# Siwa_PCB.net
KiCad netlist of a schematic drawn in Altium Designer
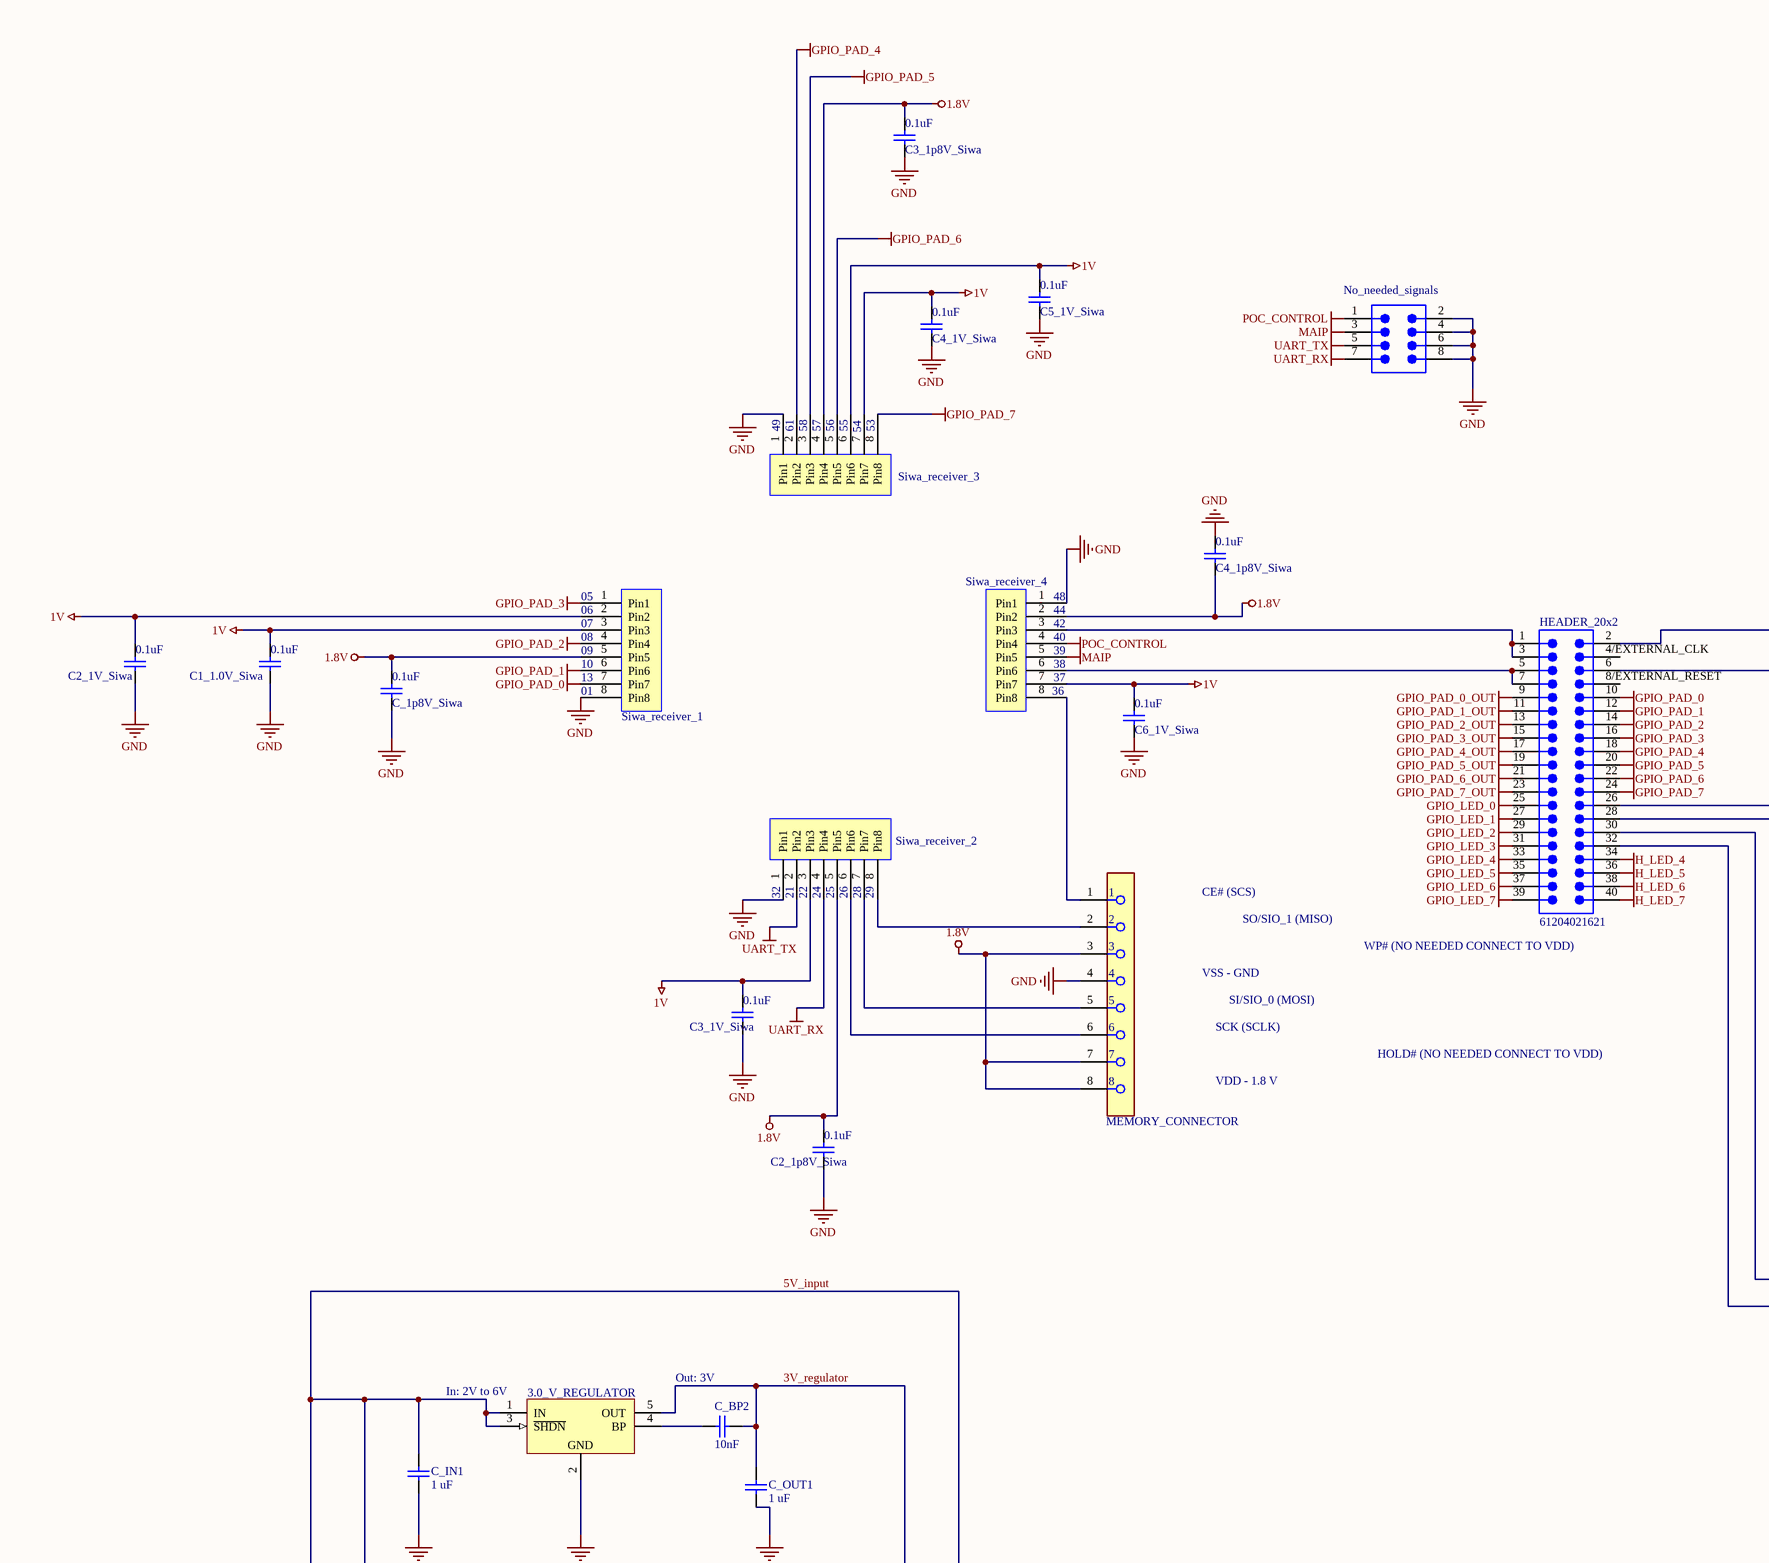
[diagram p0: Siwa_PCB.SchDoc, top left]
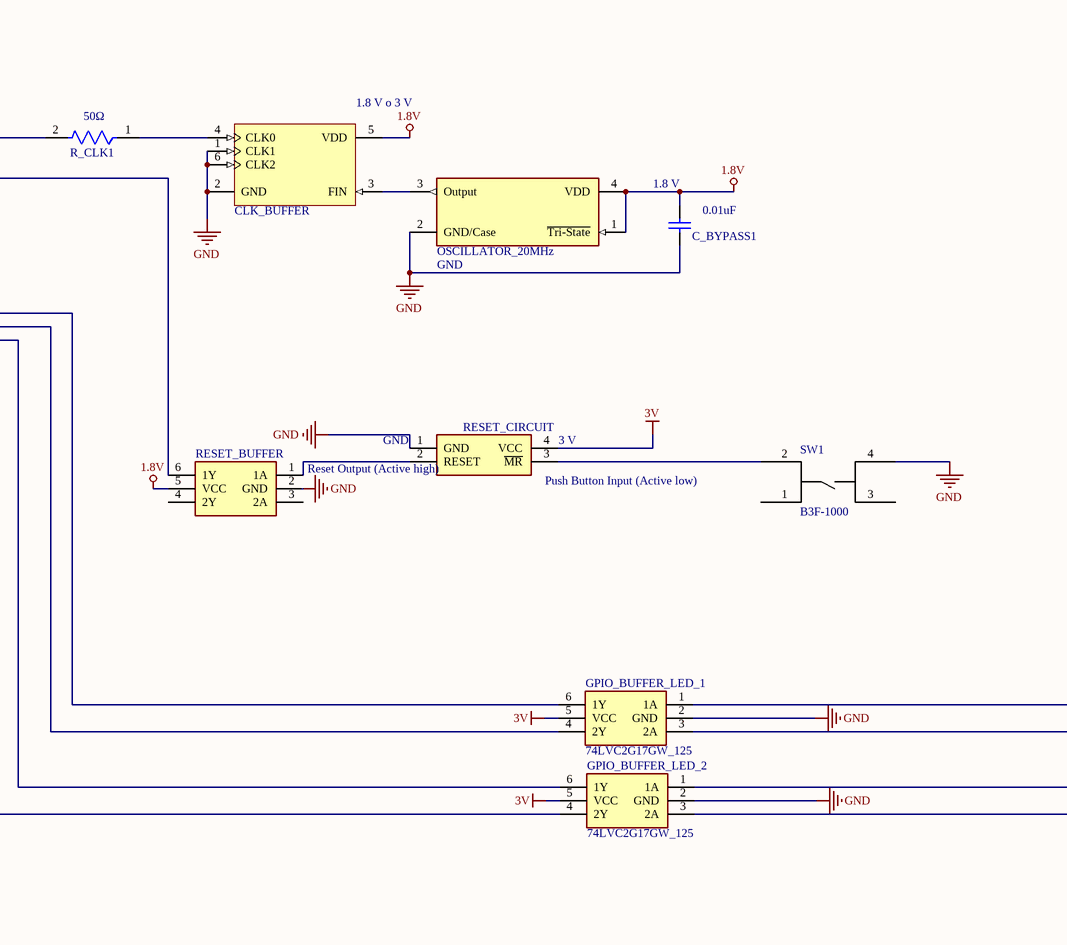
[diagram p1: Siwa_PCB.SchDoc, top right]
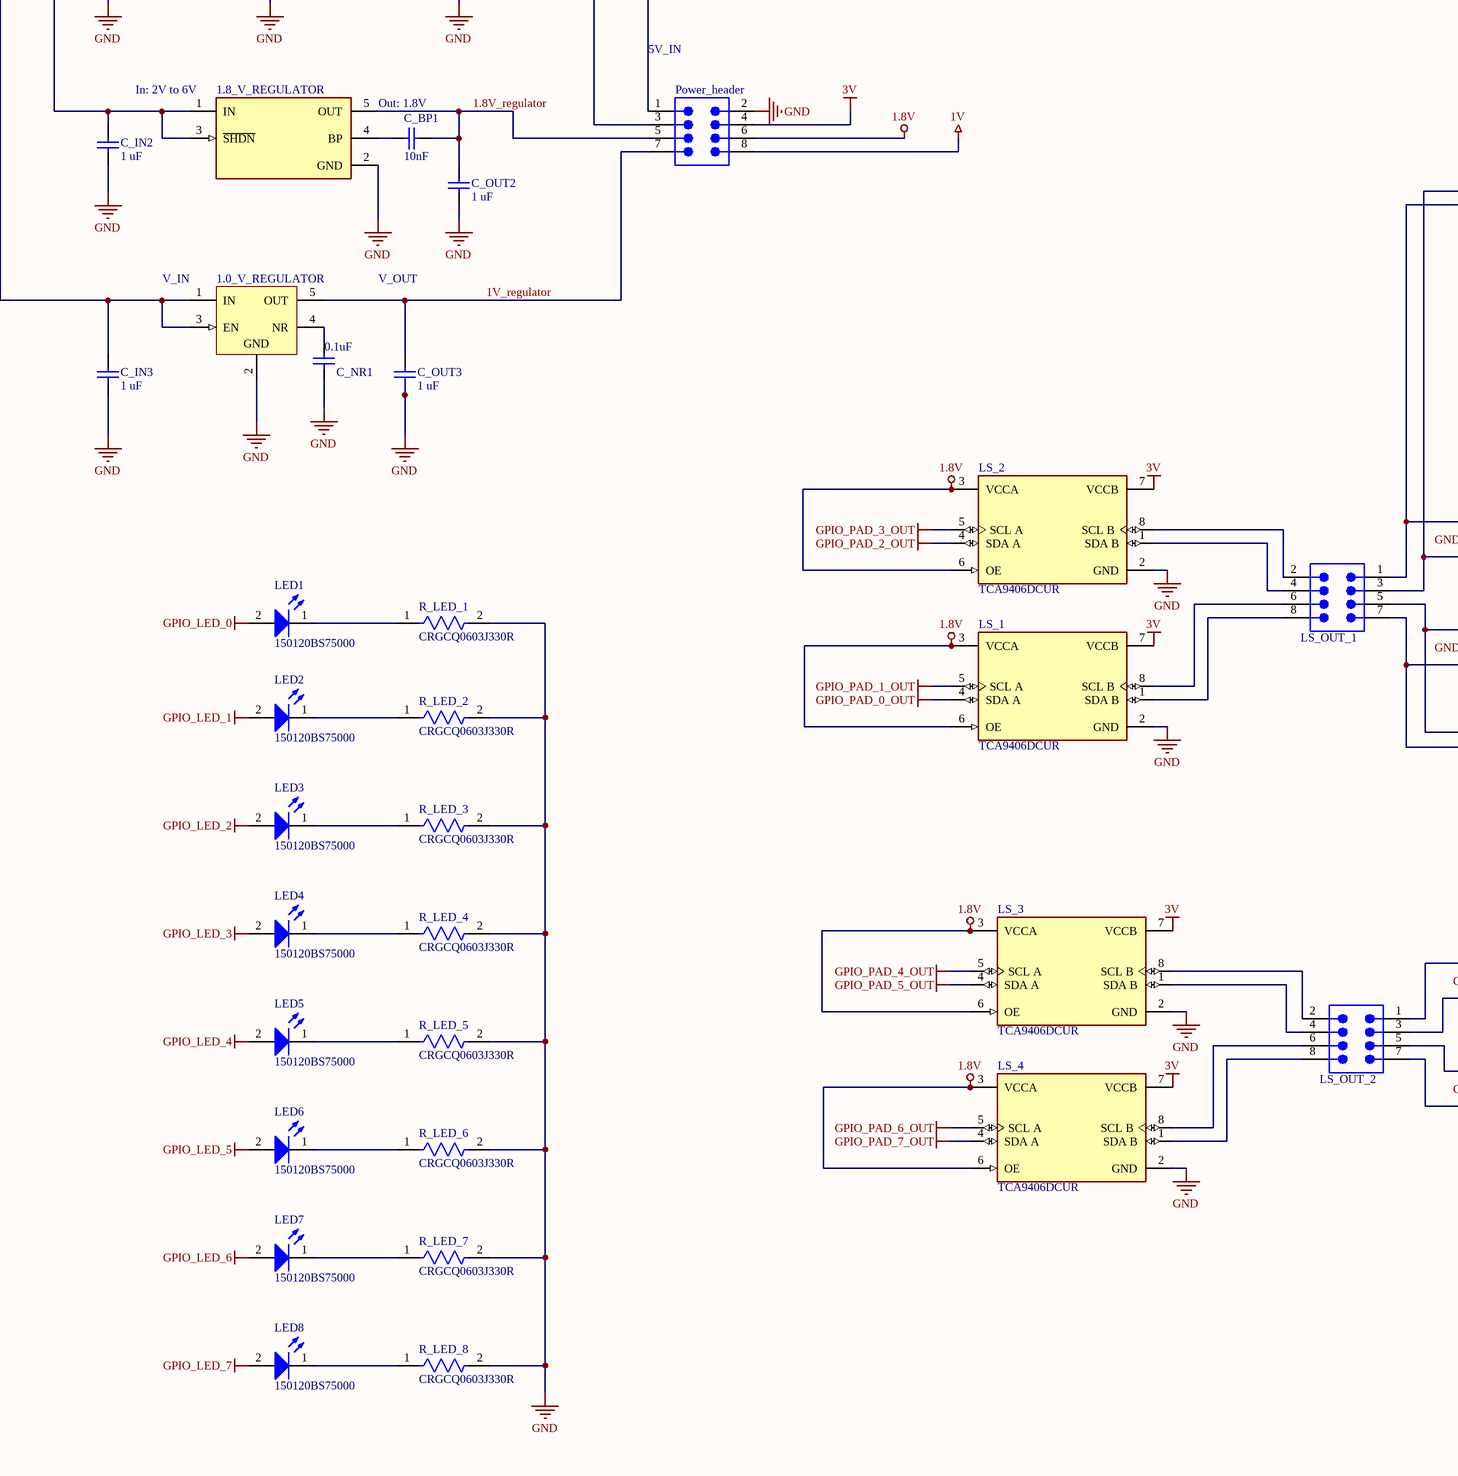
[diagram p2: Siwa_PCB.SchDoc, bottom left]
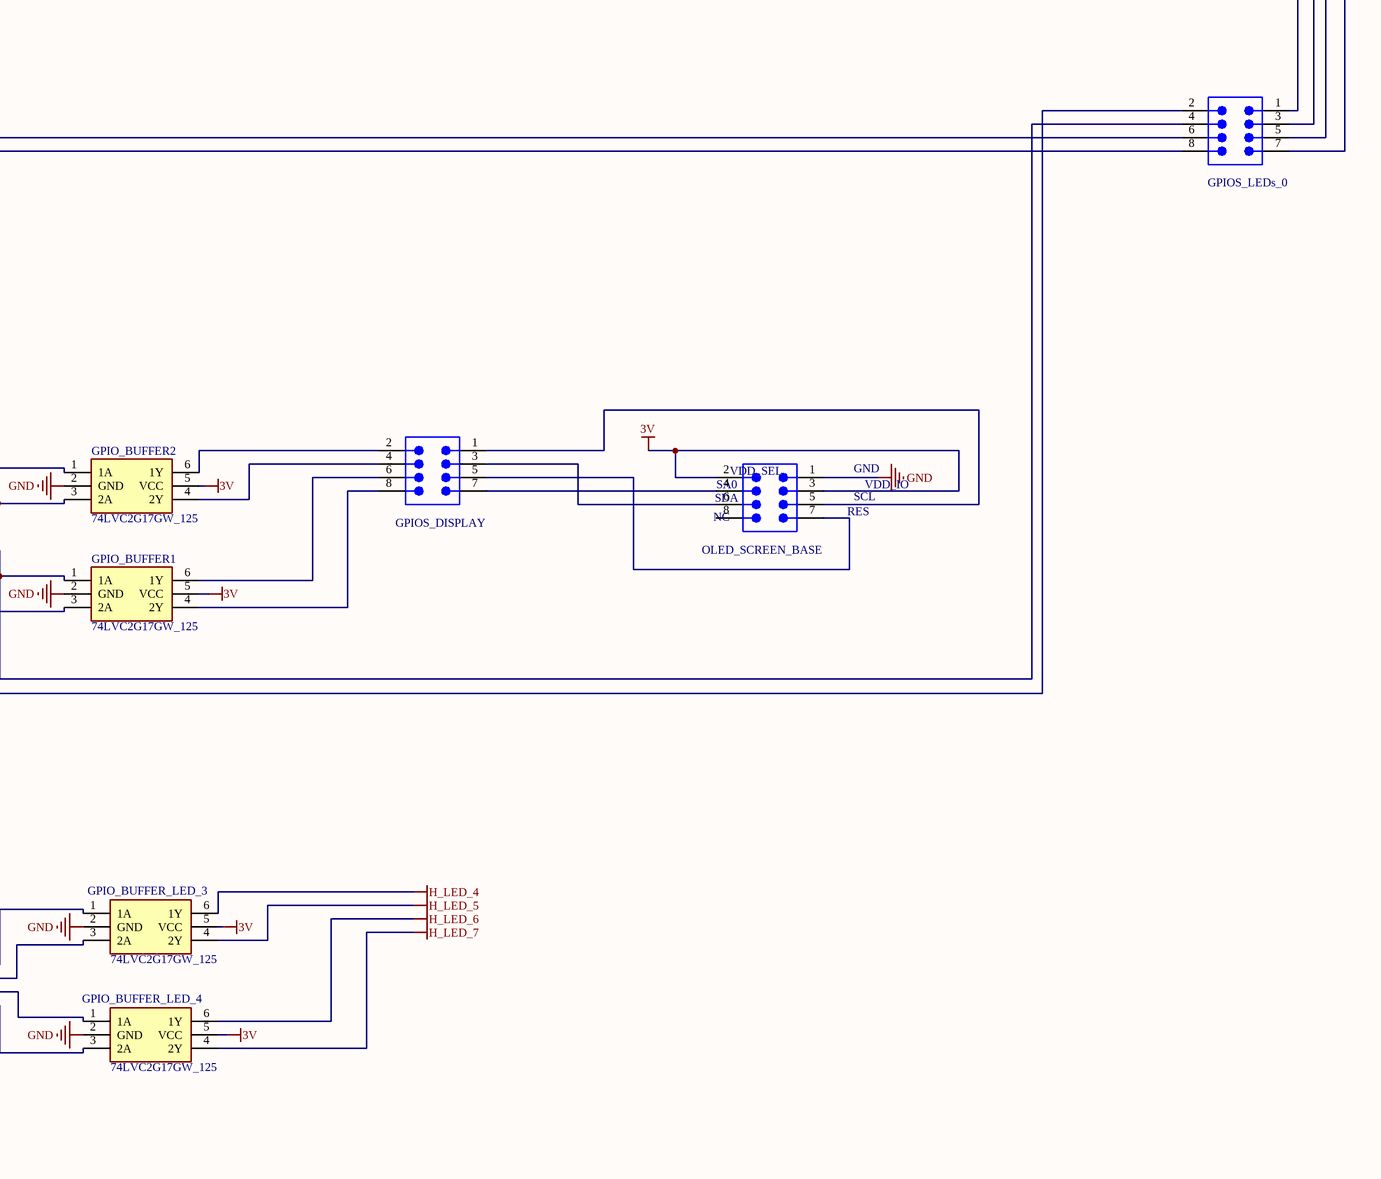
[diagram p3: Siwa_PCB.SchDoc, bottom right]

(export (version "E")
  (design (tool "Eeschema 10.0.6"))
  (components
    (comp (ref "1.0_V_REGULATOR")
      (value "TPS71710DCKT")
      (footprint "DCK0005A_M")
      (fields (field (name "MANUFACTURER") "Texas Instruments"))
      (libsource (lib "Altium Content Vault") (part "TI-TPS79NXX-YYSOT5"))
    )
    (comp (ref "1.8_V_REGULATOR")
      (value "MAX8510EXK18+T")
      (footprint "FP-X5-1-MFG")
      (description "IC REG LINEAR 1.8V 120MA SC70-5")
      (libsource (lib "Altium Content Vault") (part "355d6218c957986cfc1b3588039a240"))
    )
    (comp (ref "3.0_V_REGULATOR")
      (value "MAX8510EXK30+T")
      (footprint "X5-1_N")
      (libsource (lib "Altium Content Vault") (part "MAX-MAX8510-SOT5"))
    )
    (comp (ref "C1_1.0V_Siwa")
      (value "0.1uF")
      (footprint "CAPC1608X92X38NL15T08")
      (fields (field (name "MANUFACTURER") "Vitramon") (field (name "PART NUMBER") "VJ0603Y104KXXAP"))
      (libsource (lib "Altium Content Vault") (part "CAP"))
    )
    (comp (ref "C2_1p8V_Siwa")
      (value "0.1uF")
      (footprint "CAPC1608X92X38NL15T08")
      (fields (field (name "MANUFACTURER") "Vitramon") (field (name "PART NUMBER") "VJ0603Y104KXXAP"))
      (libsource (lib "Altium Content Vault") (part "CAP"))
    )
    (comp (ref "C2_1V_Siwa")
      (value "0.1uF")
      (footprint "CAPC1608X92X38NL15T08")
      (fields (field (name "MANUFACTURER") "Vitramon") (field (name "PART NUMBER") "VJ0603Y104KXXAP"))
      (libsource (lib "Altium Content Vault") (part "CAP"))
    )
    (comp (ref "C3_1p8V_Siwa")
      (value "0.1uF")
      (footprint "CAPC1608X92X38NL15T08")
      (fields (field (name "MANUFACTURER") "Vitramon") (field (name "PART NUMBER") "VJ0603Y104KXXAP"))
      (libsource (lib "Altium Content Vault") (part "CAP"))
    )
    (comp (ref "C3_1V_Siwa")
      (value "0.1uF")
      (footprint "CAPC1608X92X38NL15T08")
      (fields (field (name "MANUFACTURER") "Vitramon") (field (name "PART NUMBER") "VJ0603Y104KXXAP"))
      (libsource (lib "Altium Content Vault") (part "CAP"))
    )
    (comp (ref "C4_1p8V_Siwa")
      (value "0.1uF")
      (footprint "CAPC1608X92X38NL15T08")
      (fields (field (name "MANUFACTURER") "Vitramon") (field (name "PART NUMBER") "VJ0603Y104KXXAP"))
      (libsource (lib "Altium Content Vault") (part "CAP"))
    )
    (comp (ref "C4_1V_Siwa")
      (value "0.1uF")
      (footprint "CAPC1608X92X38NL15T08")
      (fields (field (name "MANUFACTURER") "Vitramon") (field (name "PART NUMBER") "VJ0603Y104KXXAP"))
      (libsource (lib "Altium Content Vault") (part "CAP"))
    )
    (comp (ref "C5_1V_Siwa")
      (value "0.1uF")
      (footprint "CAPC1608X92X38NL15T08")
      (fields (field (name "MANUFACTURER") "Vitramon") (field (name "PART NUMBER") "VJ0603Y104KXXAP"))
      (libsource (lib "Altium Content Vault") (part "CAP"))
    )
    (comp (ref "C6_1V_Siwa")
      (value "0.1uF")
      (footprint "CAPC1608X92X38NL15T08")
      (fields (field (name "MANUFACTURER") "Vitramon") (field (name "PART NUMBER") "VJ0603Y104KXXAP"))
      (libsource (lib "Altium Content Vault") (part "CAP"))
    )
    (comp (ref "CLK_BUFFER")
      (value "PL133-37TI")
      (footprint "FP-SOT23-6LD-PL-1-MFG")
      (libsource (lib "Altium Content Vault") (part "PL133-37TI"))
    )
    (comp (ref "C_1p8V_Siwa")
      (value "0.1uF")
      (footprint "CAPC1608X92X38NL15T08")
      (fields (field (name "MANUFACTURER") "Vitramon") (field (name "PART NUMBER") "VJ0603Y104KXXAP"))
      (libsource (lib "Altium Content Vault") (part "CAP"))
    )
    (comp (ref "C_BP1")
      (value "10nF")
      (footprint "CAPC1608X92X38LL15T08")
      (fields (field (name "MANUFACTURER") "Vitramon") (field (name "PART NUMBER") "VJ0603Y103JXXAC"))
      (libsource (lib "Altium Content Vault") (part "CAP"))
    )
    (comp (ref "C_BP2")
      (value "10nF")
      (footprint "CAPC1608X92X38LL15T08")
      (fields (field (name "MANUFACTURER") "Vitramon") (field (name "PART NUMBER") "VJ0603Y103JXXAC"))
      (libsource (lib "Altium Content Vault") (part "CAP"))
    )
    (comp (ref "C_BYPASS1")
      (value "0.01uF")
      (footprint "CAPC1608X92X38NL15T08")
      (fields (field (name "MANUFACTURER") "Vitramon") (field (name "PART NUMBER") "VJ0603Y103KXAAP"))
      (libsource (lib "Altium Content Vault") (part "CAP"))
    )
    (comp (ref "C_IN1")
      (value "1 uF")
      (footprint "CAPC1608X90X35LL15T15")
      (fields
        (field (name "MANUFACTURER") "AVX Interconnect / Elco")
        (field (name "PART NUMBER") "0603YG105ZAT2A")
      )
      (libsource (lib "Altium Content Vault") (part "CAP"))
    )
    (comp (ref "C_IN2")
      (value "1 uF")
      (footprint "CAPC1608X90X35LL15T15")
      (fields
        (field (name "MANUFACTURER") "AVX Interconnect / Elco")
        (field (name "PART NUMBER") "0603YG105ZAT2A")
      )
      (libsource (lib "Altium Content Vault") (part "CAP"))
    )
    (comp (ref "C_IN3")
      (value "1 uF")
      (footprint "CAPC1608X90X35LL15T15")
      (fields
        (field (name "MANUFACTURER") "AVX Interconnect / Elco")
        (field (name "PART NUMBER") "0603YG105ZAT2A")
      )
      (libsource (lib "Altium Content Vault") (part "CAP"))
    )
    (comp (ref "C_NR1")
      (value "0.1uF")
      (footprint "CAPC1608X92X38NL15T08")
      (fields (field (name "MANUFACTURER") "Vitramon") (field (name "PART NUMBER") "VJ0603Y104KXXAP"))
      (libsource (lib "Altium Content Vault") (part "CAP"))
    )
    (comp (ref "C_OUT1")
      (value "1 uF")
      (footprint "CAPC1608X90X35LL15T15")
      (fields
        (field (name "MANUFACTURER") "AVX Interconnect / Elco")
        (field (name "PART NUMBER") "0603YG105ZAT2A")
      )
      (libsource (lib "Altium Content Vault") (part "CAP"))
    )
    (comp (ref "C_OUT2")
      (value "1 uF")
      (footprint "CAPC1608X90X35LL15T15")
      (fields
        (field (name "MANUFACTURER") "AVX Interconnect / Elco")
        (field (name "PART NUMBER") "0603YG105ZAT2A")
      )
      (libsource (lib "Altium Content Vault") (part "CAP"))
    )
    (comp (ref "C_OUT3")
      (value "1 uF")
      (footprint "CAPC1608X90X35LL15T15")
      (fields
        (field (name "MANUFACTURER") "AVX Interconnect / Elco")
        (field (name "PART NUMBER") "0603YG105ZAT2A")
      )
      (libsource (lib "Altium Content Vault") (part "CAP"))
    )
    (comp (ref "GPIOS_DISPLAY")
      (value "61200821621")
      (footprint "61200821621")
      (description "Wr-bhd; 2.54MM Pitch 8 Way 2 Row Shrouded Straight Pcb Header, Surface Mount")
      (libsource (lib "Altium Content Vault") (part "Header_Male_2R_08P"))
    )
    (comp (ref "GPIOS_LEDs_0")
      (value "61200821621")
      (footprint "61200821621")
      (description "Wr-bhd; 2.54MM Pitch 8 Way 2 Row Shrouded Straight Pcb Header, Surface Mount")
      (libsource (lib "Altium Content Vault") (part "Header_Male_2R_08P"))
    )
    (comp (ref "GPIO_BUFFER1")
      (value "74LVC2G17GW_125")
      (footprint "SOT65P210X110-6N")
      (fields
        (field (name "MANUFACTURER_PART_NUMBER") "74LVC2G17GW,125")
        (field (name "MOUSER PART NUMBER") "771-LVC2G17GW125")
      )
      (libsource (lib "74LVC2G17GW_125") (part "74LVC2G17GW_125"))
    )
    (comp (ref "GPIO_BUFFER2")
      (value "74LVC2G17GW_125")
      (footprint "SOT65P210X110-6N")
      (fields
        (field (name "MANUFACTURER_PART_NUMBER") "74LVC2G17GW,125")
        (field (name "MOUSER PART NUMBER") "771-LVC2G17GW125")
      )
      (libsource (lib "74LVC2G17GW_125") (part "74LVC2G17GW_125"))
    )
    (comp (ref "GPIO_BUFFER_LED_1")
      (value "74LVC2G17GW_125")
      (footprint "SOT65P210X110-6N")
      (fields
        (field (name "MANUFACTURER_PART_NUMBER") "74LVC2G17GW,125")
        (field (name "MOUSER PART NUMBER") "771-LVC2G17GW125")
      )
      (libsource (lib "") (part "74LVC2G17GW_125_1"))
    )
    (comp (ref "GPIO_BUFFER_LED_2")
      (value "74LVC2G17GW_125")
      (footprint "SOT65P210X110-6N")
      (fields
        (field (name "MANUFACTURER_PART_NUMBER") "74LVC2G17GW,125")
        (field (name "MOUSER PART NUMBER") "771-LVC2G17GW125")
      )
      (libsource (lib "") (part "74LVC2G17GW_125_1"))
    )
    (comp (ref "GPIO_BUFFER_LED_3")
      (value "74LVC2G17GW_125")
      (footprint "SOT65P210X110-6N")
      (fields
        (field (name "MANUFACTURER_PART_NUMBER") "74LVC2G17GW,125")
        (field (name "MOUSER PART NUMBER") "771-LVC2G17GW125")
      )
      (libsource (lib "74LVC2G17GW_125") (part "74LVC2G17GW_125"))
    )
    (comp (ref "GPIO_BUFFER_LED_4")
      (value "74LVC2G17GW_125")
      (footprint "SOT65P210X110-6N")
      (fields
        (field (name "MANUFACTURER_PART_NUMBER") "74LVC2G17GW,125")
        (field (name "MOUSER PART NUMBER") "771-LVC2G17GW125")
      )
      (libsource (lib "74LVC2G17GW_125") (part "74LVC2G17GW_125"))
    )
    (comp (ref "HEADER_20x2")
      (value "61204021621")
      (footprint "61204021621")
      (description "WR-BHD Straight Male, Box Header, Through Hole, 2 Rows, 40 Contacts, 2.54mm Pitch")
      (libsource (lib "Altium Content Vault") (part "Header_Male_2R_40P"))
    )
    (comp (ref "LED1")
      (value "150120BS75000")
      (footprint "WL-SMCW_1206_150120xx75000")
      (description "WL-SMCW SMT Mono-Color Chip LED Waterclear")
      (libsource (lib "Altium Content Vault") (part "LED_Blue_2A-1K"))
    )
    (comp (ref "LED2")
      (value "150120BS75000")
      (footprint "WL-SMCW_1206_150120xx75000")
      (description "WL-SMCW SMT Mono-Color Chip LED Waterclear")
      (libsource (lib "Altium Content Vault") (part "LED_Blue_2A-1K"))
    )
    (comp (ref "LED3")
      (value "150120BS75000")
      (footprint "WL-SMCW_1206_150120xx75000")
      (description "WL-SMCW SMT Mono-Color Chip LED Waterclear")
      (libsource (lib "Altium Content Vault") (part "LED_Blue_2A-1K"))
    )
    (comp (ref "LED4")
      (value "150120BS75000")
      (footprint "WL-SMCW_1206_150120xx75000")
      (description "WL-SMCW SMT Mono-Color Chip LED Waterclear")
      (libsource (lib "Altium Content Vault") (part "LED_Blue_2A-1K"))
    )
    (comp (ref "LED5")
      (value "150120BS75000")
      (footprint "WL-SMCW_1206_150120xx75000")
      (description "WL-SMCW SMT Mono-Color Chip LED Waterclear")
      (libsource (lib "Altium Content Vault") (part "LED_Blue_2A-1K"))
    )
    (comp (ref "LED6")
      (value "150120BS75000")
      (footprint "WL-SMCW_1206_150120xx75000")
      (description "WL-SMCW SMT Mono-Color Chip LED Waterclear")
      (libsource (lib "Altium Content Vault") (part "LED_Blue_2A-1K"))
    )
    (comp (ref "LED7")
      (value "150120BS75000")
      (footprint "WL-SMCW_1206_150120xx75000")
      (description "WL-SMCW SMT Mono-Color Chip LED Waterclear")
      (libsource (lib "Altium Content Vault") (part "LED_Blue_2A-1K"))
    )
    (comp (ref "LED8")
      (value "150120BS75000")
      (footprint "WL-SMCW_1206_150120xx75000")
      (description "WL-SMCW SMT Mono-Color Chip LED Waterclear")
      (libsource (lib "Altium Content Vault") (part "LED_Blue_2A-1K"))
    )
    (comp (ref "LS_1")
      (value "TCA9406DCUR")
      (footprint "FP-DCU0008A-IPC_B")
      (description "IC TRNSLTR BIDIRECTIONAL US8")
      (libsource (lib "Altium Content Vault") (part "2e2e7ab415e70eec0fdfb76e593e2e7"))
    )
    (comp (ref "LS_2")
      (value "TCA9406DCUR")
      (footprint "FP-DCU0008A-IPC_B")
      (description "IC TRNSLTR BIDIRECTIONAL US8")
      (libsource (lib "Altium Content Vault") (part "2e2e7ab415e70eec0fdfb76e593e2e7"))
    )
    (comp (ref "LS_3")
      (value "TCA9406DCUR")
      (footprint "FP-DCU0008A-IPC_B")
      (description "IC TRNSLTR BIDIRECTIONAL US8")
      (libsource (lib "Altium Content Vault") (part "2e2e7ab415e70eec0fdfb76e593e2e7"))
    )
    (comp (ref "LS_4")
      (value "TCA9406DCUR")
      (footprint "FP-DCU0008A-IPC_B")
      (description "IC TRNSLTR BIDIRECTIONAL US8")
      (libsource (lib "Altium Content Vault") (part "2e2e7ab415e70eec0fdfb76e593e2e7"))
    )
    (comp (ref "LS_OUT_1")
      (value "61200821621")
      (footprint "61200821621")
      (description "Wr-bhd; 2.54MM Pitch 8 Way 2 Row Shrouded Straight Pcb Header, Surface Mount")
      (libsource (lib "Altium Content Vault") (part "Header_Male_2R_08P"))
    )
    (comp (ref "LS_OUT_2")
      (value "61200821621")
      (footprint "61200821621")
      (description "Wr-bhd; 2.54MM Pitch 8 Way 2 Row Shrouded Straight Pcb Header, Surface Mount")
      (libsource (lib "Altium Content Vault") (part "Header_Male_2R_08P"))
    )
    (comp (ref "MEMORY_CONNECTOR")
      (value "DIP8_base")
      (footprint "FP-1-2199298-2-MFG")
      (description "CONN IC DIP SOCKET 8POS TIN")
      (libsource (lib "Altium Content Vault") (part "b0a0b555dd3abf3683e7c330df25cc4"))
    )
    (comp (ref "No_needed_signals")
      (value "61200821621")
      (footprint "61200821621")
      (description "Wr-bhd; 2.54MM Pitch 8 Way 2 Row Shrouded Straight Pcb Header, Surface Mount")
      (libsource (lib "Altium Content Vault") (part "Header_Male_2R_08P"))
    )
    (comp (ref "OLED_SCREEN_BASE")
      (value "61200821621")
      (footprint "61200821621")
      (description "Wr-bhd; 2.54MM Pitch 8 Way 2 Row Shrouded Straight Pcb Header, Surface Mount")
      (libsource (lib "Altium Content Vault") (part "Header_Male_2R_08P"))
    )
    (comp (ref "OSCILLATOR_20MHz")
      (value "ASE3-20.000MHZ-KT")
      (footprint "FP-ASE3-MFG")
      (description "XTAL OSC XO 20.0000MHZ CMOS SMD")
      (libsource (lib "Altium Content Vault") (part "37c4c26fe5ae6223af2046a137c0b30"))
    )
    (comp (ref "Power_header")
      (value "61200821621")
      (footprint "61200821621")
      (description "Wr-bhd; 2.54MM Pitch 8 Way 2 Row Shrouded Straight Pcb Header, Surface Mount")
      (libsource (lib "Altium Content Vault") (part "Header_Male_2R_08P"))
    )
    (comp (ref "RESET_BUFFER")
      (value "74LVC2G17GW_125")
      (footprint "SOT65P210X110-6N")
      (fields
        (field (name "MANUFACTURER_PART_NUMBER") "74LVC2G17GW,125")
        (field (name "MOUSER PART NUMBER") "771-LVC2G17GW125")
      )
      (libsource (lib "") (part "74LVC2G17GW_125_1"))
    )
    (comp (ref "RESET_CIRCUIT")
      (value "APX812-29UG-7")
      (footprint "APX81229UG7")
      (description "Supervisor Push-Pull, Totem Pole 1 Channel SOT-143 , 2.93V , 140ms , -40C ~ 85C (TA)")
      (fields (field (name "MOUSER PART NUMBER") "621-APX812-29UG-7"))
      (libsource (lib "APX812-29UG-7") (part "APX812-29UG-7"))
    )
    (comp (ref "R_CLK1")
      (value "50Ω")
      (footprint "FP-D12-CRCW0805-MFG")
      (description "CRCW080550R0FKTA Res Thick Film 0805 50 Ohm 1% 0.125W(1/8W) ±100ppm/C Pad SMD Automotive T/R")
      (fields (field (name "TOLERANCE") "1%"))
      (libsource (lib "Altium Content Vault") (part "1029c3af85768c4190bb7ad29bc67b5"))
    )
    (comp (ref "R_LED_1")
      (value "CRGCQ0603J330R")
      (footprint "FP-CRGCQ0603-IPC_C")
      (description "CRGCQ 0603 330R 5%")
      (fields
        (field (name "OCTOPART") "https://octopart.com/crgcq0603j330r-te+connectivity-91018118")
        (field (name "MANUFACTURER") "TE Connectivity")
      )
      (libsource (lib "Altium Content Vault") (part "1029c3af85768c4190bb7ad29bc67b5"))
    )
    (comp (ref "R_LED_2")
      (value "CRGCQ0603J330R")
      (footprint "FP-CRGCQ0603-IPC_C")
      (description "CRGCQ 0603 330R 5%")
      (fields
        (field (name "OCTOPART") "https://octopart.com/crgcq0603j330r-te+connectivity-91018118")
        (field (name "MANUFACTURER") "TE Connectivity")
      )
      (libsource (lib "Altium Content Vault") (part "1029c3af85768c4190bb7ad29bc67b5"))
    )
    (comp (ref "R_LED_3")
      (value "CRGCQ0603J330R")
      (footprint "FP-CRGCQ0603-IPC_C")
      (description "CRGCQ 0603 330R 5%")
      (fields
        (field (name "OCTOPART") "https://octopart.com/crgcq0603j330r-te+connectivity-91018118")
        (field (name "MANUFACTURER") "TE Connectivity")
      )
      (libsource (lib "Altium Content Vault") (part "1029c3af85768c4190bb7ad29bc67b5"))
    )
    (comp (ref "R_LED_4")
      (value "CRGCQ0603J330R")
      (footprint "FP-CRGCQ0603-IPC_C")
      (description "CRGCQ 0603 330R 5%")
      (fields
        (field (name "OCTOPART") "https://octopart.com/crgcq0603j330r-te+connectivity-91018118")
        (field (name "MANUFACTURER") "TE Connectivity")
      )
      (libsource (lib "Altium Content Vault") (part "1029c3af85768c4190bb7ad29bc67b5"))
    )
    (comp (ref "R_LED_5")
      (value "CRGCQ0603J330R")
      (footprint "FP-CRGCQ0603-IPC_C")
      (description "CRGCQ 0603 330R 5%")
      (fields
        (field (name "OCTOPART") "https://octopart.com/crgcq0603j330r-te+connectivity-91018118")
        (field (name "MANUFACTURER") "TE Connectivity")
      )
      (libsource (lib "Altium Content Vault") (part "1029c3af85768c4190bb7ad29bc67b5"))
    )
    (comp (ref "R_LED_6")
      (value "CRGCQ0603J330R")
      (footprint "FP-CRGCQ0603-IPC_C")
      (description "CRGCQ 0603 330R 5%")
      (fields
        (field (name "OCTOPART") "https://octopart.com/crgcq0603j330r-te+connectivity-91018118")
        (field (name "MANUFACTURER") "TE Connectivity")
      )
      (libsource (lib "Altium Content Vault") (part "1029c3af85768c4190bb7ad29bc67b5"))
    )
    (comp (ref "R_LED_7")
      (value "CRGCQ0603J330R")
      (footprint "FP-CRGCQ0603-IPC_C")
      (description "CRGCQ 0603 330R 5%")
      (fields
        (field (name "OCTOPART") "https://octopart.com/crgcq0603j330r-te+connectivity-91018118")
        (field (name "MANUFACTURER") "TE Connectivity")
      )
      (libsource (lib "Altium Content Vault") (part "1029c3af85768c4190bb7ad29bc67b5"))
    )
    (comp (ref "R_LED_8")
      (value "CRGCQ0603J330R")
      (footprint "FP-CRGCQ0603-IPC_C")
      (description "CRGCQ 0603 330R 5%")
      (fields
        (field (name "OCTOPART") "https://octopart.com/crgcq0603j330r-te+connectivity-91018118")
        (field (name "MANUFACTURER") "TE Connectivity")
      )
      (libsource (lib "Altium Content Vault") (part "1029c3af85768c4190bb7ad29bc67b5"))
    )
    (comp (ref "Siwa_receiver_1")
      (value "HEADER 8P 2.54mm")
      (footprint "PPTC081LFBN-RC")
      (libsource (lib "") (part "PPTC081LFBN-RC_3"))
    )
    (comp (ref "Siwa_receiver_2")
      (value "HEADER 8P 2.54mm")
      (footprint "PPTC081LFBN-RC")
      (libsource (lib "PPTC081LFBN-RC") (part "PPTC081LFBN-RC"))
    )
    (comp (ref "Siwa_receiver_3")
      (value "HEADER 8P 2.54mm")
      (footprint "PPTC081LFBN-RC")
      (libsource (lib "") (part "PPTC081LFBN-RC_2"))
    )
    (comp (ref "Siwa_receiver_4")
      (value "HEADER 8P 2.54mm")
      (footprint "PPTC081LFBN-RC")
      (libsource (lib "") (part "PPTC081LFBN-RC_1"))
    )
    (comp (ref "SW1")
      (value "B3F-1000")
      (footprint "PCBComponent_1")
      (libsource (lib "B3F-1000S") (part "B3F-1000S"))
    )
  )
  (nets
    (net (code "1") (name "/1.8V_regulator") (class "Default")
      (node (ref "1.8_V_REGULATOR") (pin "5") (pinfunction "OUT_5") (pintype "power_in"))
      (node (ref "C_BP1") (pin "2") (pinfunction "2_2") (pintype "passive"))
      (node (ref "C_OUT2") (pin "2") (pinfunction "2_2") (pintype "passive"))
      (node (ref "Power_header") (pin "5") (pinfunction "5_5") (pintype "passive"))
    )
    (net (code "2") (name "/1V_regulator") (class "Default")
      (node (ref "1.0_V_REGULATOR") (pin "5") (pinfunction "OUT_5") (pintype "power_in"))
      (node (ref "C_OUT3") (pin "2") (pinfunction "2_2") (pintype "passive"))
      (node (ref "Power_header") (pin "7") (pinfunction "7_7") (pintype "passive"))
    )
    (net (code "3") (name "/3V_regulator") (class "Default")
      (node (ref "3.0_V_REGULATOR") (pin "5") (pinfunction "OUT_5") (pintype "power_in"))
      (node (ref "C_BP2") (pin "2") (pinfunction "2_2") (pintype "passive"))
      (node (ref "C_OUT1") (pin "2") (pinfunction "2_2") (pintype "passive"))
      (node (ref "Power_header") (pin "3") (pinfunction "3_3") (pintype "passive"))
    )
    (net (code "4") (name "/5V_input") (class "Default")
      (node (ref "1.0_V_REGULATOR") (pin "1") (pinfunction "IN_1") (pintype "power_in"))
      (node (ref "1.0_V_REGULATOR") (pin "3") (pinfunction "EN_3") (pintype "input"))
      (node (ref "1.8_V_REGULATOR") (pin "1") (pinfunction "IN_1") (pintype "power_in"))
      (node (ref "1.8_V_REGULATOR") (pin "3") (pinfunction "~{SHDN}_3") (pintype "input"))
      (node (ref "3.0_V_REGULATOR") (pin "1") (pinfunction "IN_1") (pintype "power_in"))
      (node (ref "3.0_V_REGULATOR") (pin "3") (pinfunction "~{SHDN}_3") (pintype "input"))
      (node (ref "C_IN1") (pin "2") (pinfunction "2_2") (pintype "passive"))
      (node (ref "C_IN2") (pin "2") (pinfunction "2_2") (pintype "passive"))
      (node (ref "C_IN3") (pin "2") (pinfunction "2_2") (pintype "passive"))
      (node (ref "Power_header") (pin "1") (pinfunction "1_1") (pintype "passive"))
    )
    (net (code "5") (name "1.8V") (class "Default")
      (node (ref "C2_1p8V_Siwa") (pin "2") (pinfunction "2_2") (pintype "passive"))
      (node (ref "C3_1p8V_Siwa") (pin "2") (pinfunction "2_2") (pintype "passive"))
      (node (ref "C4_1p8V_Siwa") (pin "1") (pinfunction "1_1") (pintype "passive"))
      (node (ref "CLK_BUFFER") (pin "5") (pinfunction "VDD_5") (pintype "power_in"))
      (node (ref "C_1p8V_Siwa") (pin "2") (pinfunction "2_2") (pintype "passive"))
      (node (ref "C_BYPASS1") (pin "2") (pinfunction "2_2") (pintype "passive"))
      (node (ref "LS_1") (pin "3") (pinfunction "VCCA_3") (pintype "power_in"))
      (node (ref "LS_1") (pin "6") (pinfunction "OE_6") (pintype "input"))
      (node (ref "LS_2") (pin "3") (pinfunction "VCCA_3") (pintype "power_in"))
      (node (ref "LS_2") (pin "6") (pinfunction "OE_6") (pintype "input"))
      (node (ref "LS_3") (pin "3") (pinfunction "VCCA_3") (pintype "power_in"))
      (node (ref "LS_3") (pin "6") (pinfunction "OE_6") (pintype "input"))
      (node (ref "LS_4") (pin "3") (pinfunction "VCCA_3") (pintype "power_in"))
      (node (ref "LS_4") (pin "6") (pinfunction "OE_6") (pintype "input"))
      (node (ref "MEMORY_CONNECTOR") (pin "3") (pinfunction "3_3") (pintype "passive"))
      (node (ref "MEMORY_CONNECTOR") (pin "7") (pinfunction "7_7") (pintype "passive"))
      (node (ref "MEMORY_CONNECTOR") (pin "8") (pinfunction "8_8") (pintype "passive"))
      (node (ref "OSCILLATOR_20MHz") (pin "1") (pinfunction "~{Tri-State}_1") (pintype "input"))
      (node (ref "OSCILLATOR_20MHz") (pin "4") (pinfunction "VDD_4") (pintype "power_in"))
      (node (ref "Power_header") (pin "6") (pinfunction "6_6") (pintype "passive"))
      (node (ref "RESET_BUFFER") (pin "5") (pinfunction "VCC_5") (pintype "passive"))
      (node (ref "Siwa_receiver_1") (pin "5") (pinfunction "Pin5_5") (pintype "passive"))
      (node (ref "Siwa_receiver_2") (pin "5") (pinfunction "Pin5_5") (pintype "passive"))
      (node (ref "Siwa_receiver_3") (pin "4") (pinfunction "Pin4_4") (pintype "passive"))
      (node (ref "Siwa_receiver_4") (pin "2") (pinfunction "Pin2_2") (pintype "passive"))
    )
    (net (code "6") (name "1V") (class "Default")
      (node (ref "C1_1.0V_Siwa") (pin "2") (pinfunction "2_2") (pintype "passive"))
      (node (ref "C2_1V_Siwa") (pin "2") (pinfunction "2_2") (pintype "passive"))
      (node (ref "C3_1V_Siwa") (pin "2") (pinfunction "2_2") (pintype "passive"))
      (node (ref "C4_1V_Siwa") (pin "2") (pinfunction "2_2") (pintype "passive"))
      (node (ref "C5_1V_Siwa") (pin "2") (pinfunction "2_2") (pintype "passive"))
      (node (ref "C6_1V_Siwa") (pin "2") (pinfunction "2_2") (pintype "passive"))
      (node (ref "Power_header") (pin "8") (pinfunction "8_8") (pintype "passive"))
      (node (ref "Siwa_receiver_1") (pin "2") (pinfunction "Pin2_2") (pintype "passive"))
      (node (ref "Siwa_receiver_1") (pin "3") (pinfunction "Pin3_3") (pintype "passive"))
      (node (ref "Siwa_receiver_2") (pin "3") (pinfunction "Pin3_3") (pintype "passive"))
      (node (ref "Siwa_receiver_3") (pin "6") (pinfunction "Pin6_6") (pintype "passive"))
      (node (ref "Siwa_receiver_3") (pin "7") (pinfunction "Pin7_7") (pintype "passive"))
      (node (ref "Siwa_receiver_4") (pin "7") (pinfunction "Pin7_7") (pintype "passive"))
    )
    (net (code "7") (name "3V") (class "Default")
      (node (ref "GPIO_BUFFER1") (pin "5") (pinfunction "VCC_5") (pintype "passive"))
      (node (ref "GPIO_BUFFER2") (pin "5") (pinfunction "VCC_5") (pintype "passive"))
      (node (ref "GPIO_BUFFER_LED_1") (pin "5") (pinfunction "VCC_5") (pintype "passive"))
      (node (ref "GPIO_BUFFER_LED_2") (pin "5") (pinfunction "VCC_5") (pintype "passive"))
      (node (ref "GPIO_BUFFER_LED_3") (pin "5") (pinfunction "VCC_5") (pintype "passive"))
      (node (ref "GPIO_BUFFER_LED_4") (pin "5") (pinfunction "VCC_5") (pintype "passive"))
      (node (ref "LS_1") (pin "7") (pinfunction "VCCB_7") (pintype "power_in"))
      (node (ref "LS_2") (pin "7") (pinfunction "VCCB_7") (pintype "power_in"))
      (node (ref "LS_3") (pin "7") (pinfunction "VCCB_7") (pintype "power_in"))
      (node (ref "LS_4") (pin "7") (pinfunction "VCCB_7") (pintype "power_in"))
      (node (ref "OLED_SCREEN_BASE") (pin "2") (pinfunction "2_2") (pintype "passive"))
      (node (ref "OLED_SCREEN_BASE") (pin "3") (pinfunction "3_3") (pintype "passive"))
      (node (ref "Power_header") (pin "4") (pinfunction "4_4") (pintype "passive"))
      (node (ref "RESET_CIRCUIT") (pin "4") (pinfunction "VCC_4") (pintype "passive"))
    )
    (net (code "8") (name "GND") (class "Default")
      (node (ref "1.0_V_REGULATOR") (pin "2") (pinfunction "GND_2") (pintype "power_in"))
      (node (ref "1.8_V_REGULATOR") (pin "2") (pinfunction "GND_2") (pintype "power_in"))
      (node (ref "3.0_V_REGULATOR") (pin "2") (pinfunction "GND_2") (pintype "power_in"))
      (node (ref "C1_1.0V_Siwa") (pin "1") (pinfunction "1_1") (pintype "passive"))
      (node (ref "C2_1V_Siwa") (pin "1") (pinfunction "1_1") (pintype "passive"))
      (node (ref "C2_1p8V_Siwa") (pin "1") (pinfunction "1_1") (pintype "passive"))
      (node (ref "C3_1V_Siwa") (pin "1") (pinfunction "1_1") (pintype "passive"))
      (node (ref "C3_1p8V_Siwa") (pin "1") (pinfunction "1_1") (pintype "passive"))
      (node (ref "C4_1V_Siwa") (pin "1") (pinfunction "1_1") (pintype "passive"))
      (node (ref "C4_1p8V_Siwa") (pin "2") (pinfunction "2_2") (pintype "passive"))
      (node (ref "C5_1V_Siwa") (pin "1") (pinfunction "1_1") (pintype "passive"))
      (node (ref "C6_1V_Siwa") (pin "1") (pinfunction "1_1") (pintype "passive"))
      (node (ref "CLK_BUFFER") (pin "1") (pinfunction "CLK1_1") (pintype "input"))
      (node (ref "CLK_BUFFER") (pin "2") (pinfunction "GND_2") (pintype "power_in"))
      (node (ref "CLK_BUFFER") (pin "6") (pinfunction "CLK2_6") (pintype "input"))
      (node (ref "C_1p8V_Siwa") (pin "1") (pinfunction "1_1") (pintype "passive"))
      (node (ref "C_BYPASS1") (pin "1") (pinfunction "1_1") (pintype "passive"))
      (node (ref "C_IN1") (pin "1") (pinfunction "1_1") (pintype "passive"))
      (node (ref "C_IN2") (pin "1") (pinfunction "1_1") (pintype "passive"))
      (node (ref "C_IN3") (pin "1") (pinfunction "1_1") (pintype "passive"))
      (node (ref "C_NR1") (pin "1") (pinfunction "1_1") (pintype "passive"))
      (node (ref "C_OUT1") (pin "1") (pinfunction "1_1") (pintype "passive"))
      (node (ref "C_OUT2") (pin "1") (pinfunction "1_1") (pintype "passive"))
      (node (ref "C_OUT3") (pin "1") (pinfunction "1_1") (pintype "passive"))
      (node (ref "GPIO_BUFFER1") (pin "2") (pinfunction "GND_2") (pintype "passive"))
      (node (ref "GPIO_BUFFER2") (pin "2") (pinfunction "GND_2") (pintype "passive"))
      (node (ref "GPIO_BUFFER_LED_1") (pin "2") (pinfunction "GND_2") (pintype "passive"))
      (node (ref "GPIO_BUFFER_LED_2") (pin "2") (pinfunction "GND_2") (pintype "passive"))
      (node (ref "GPIO_BUFFER_LED_3") (pin "2") (pinfunction "GND_2") (pintype "passive"))
      (node (ref "GPIO_BUFFER_LED_4") (pin "2") (pinfunction "GND_2") (pintype "passive"))
      (node (ref "LS_1") (pin "2") (pinfunction "GND_2") (pintype "power_in"))
      (node (ref "LS_2") (pin "2") (pinfunction "GND_2") (pintype "power_in"))
      (node (ref "LS_3") (pin "2") (pinfunction "GND_2") (pintype "power_in"))
      (node (ref "LS_4") (pin "2") (pinfunction "GND_2") (pintype "power_in"))
      (node (ref "MEMORY_CONNECTOR") (pin "4") (pinfunction "4_4") (pintype "passive"))
      (node (ref "No_needed_signals") (pin "2") (pinfunction "2_2") (pintype "passive"))
      (node (ref "No_needed_signals") (pin "4") (pinfunction "4_4") (pintype "passive"))
      (node (ref "No_needed_signals") (pin "6") (pinfunction "6_6") (pintype "passive"))
      (node (ref "No_needed_signals") (pin "8") (pinfunction "8_8") (pintype "passive"))
      (node (ref "OLED_SCREEN_BASE") (pin "1") (pinfunction "1_1") (pintype "passive"))
      (node (ref "OSCILLATOR_20MHz") (pin "2") (pinfunction "GND/Case_2") (pintype "power_in"))
      (node (ref "Power_header") (pin "2") (pinfunction "2_2") (pintype "passive"))
      (node (ref "RESET_BUFFER") (pin "2") (pinfunction "GND_2") (pintype "passive"))
      (node (ref "RESET_CIRCUIT") (pin "1") (pinfunction "GND_1") (pintype "passive"))
      (node (ref "R_LED_1") (pin "2") (pinfunction "2_2") (pintype "passive"))
      (node (ref "R_LED_2") (pin "2") (pinfunction "2_2") (pintype "passive"))
      (node (ref "R_LED_3") (pin "2") (pinfunction "2_2") (pintype "passive"))
      (node (ref "R_LED_4") (pin "2") (pinfunction "2_2") (pintype "passive"))
      (node (ref "R_LED_5") (pin "2") (pinfunction "2_2") (pintype "passive"))
      (node (ref "R_LED_6") (pin "2") (pinfunction "2_2") (pintype "passive"))
      (node (ref "R_LED_7") (pin "2") (pinfunction "2_2") (pintype "passive"))
      (node (ref "R_LED_8") (pin "2") (pinfunction "2_2") (pintype "passive"))
      (node (ref "SW1") (pin "4") (pinfunction "P4_4") (pintype "passive"))
      (node (ref "Siwa_receiver_1") (pin "8") (pinfunction "Pin8_8") (pintype "passive"))
      (node (ref "Siwa_receiver_2") (pin "1") (pinfunction "Pin1_1") (pintype "passive"))
      (node (ref "Siwa_receiver_3") (pin "1") (pinfunction "Pin1_1") (pintype "passive"))
      (node (ref "Siwa_receiver_4") (pin "1") (pinfunction "Pin1_1") (pintype "passive"))
    )
    (net (code "9") (name "GPIO_LED_0") (class "Default")
      (node (ref "HEADER_20x2") (pin "25") (pinfunction "25_25") (pintype "passive"))
      (node (ref "LED1") (pin "2") (pinfunction "A_2") (pintype "passive"))
    )
    (net (code "10") (name "GPIO_LED_1") (class "Default")
      (node (ref "HEADER_20x2") (pin "27") (pinfunction "27_27") (pintype "passive"))
      (node (ref "LED2") (pin "2") (pinfunction "A_2") (pintype "passive"))
    )
    (net (code "11") (name "GPIO_LED_2") (class "Default")
      (node (ref "HEADER_20x2") (pin "29") (pinfunction "29_29") (pintype "passive"))
      (node (ref "LED3") (pin "2") (pinfunction "A_2") (pintype "passive"))
    )
    (net (code "12") (name "GPIO_LED_3") (class "Default")
      (node (ref "HEADER_20x2") (pin "31") (pinfunction "31_31") (pintype "passive"))
      (node (ref "LED4") (pin "2") (pinfunction "A_2") (pintype "passive"))
    )
    (net (code "13") (name "GPIO_LED_4") (class "Default")
      (node (ref "HEADER_20x2") (pin "33") (pinfunction "33_33") (pintype "passive"))
      (node (ref "LED5") (pin "2") (pinfunction "A_2") (pintype "passive"))
    )
    (net (code "14") (name "GPIO_LED_5") (class "Default")
      (node (ref "HEADER_20x2") (pin "35") (pinfunction "35_35") (pintype "passive"))
      (node (ref "LED6") (pin "2") (pinfunction "A_2") (pintype "passive"))
    )
    (net (code "15") (name "GPIO_LED_6") (class "Default")
      (node (ref "HEADER_20x2") (pin "37") (pinfunction "37_37") (pintype "passive"))
      (node (ref "LED7") (pin "2") (pinfunction "A_2") (pintype "passive"))
    )
    (net (code "16") (name "GPIO_LED_7") (class "Default")
      (node (ref "HEADER_20x2") (pin "39") (pinfunction "39_39") (pintype "passive"))
      (node (ref "LED8") (pin "2") (pinfunction "A_2") (pintype "passive"))
    )
    (net (code "17") (name "GPIO_PAD_0") (class "Default")
      (node (ref "HEADER_20x2") (pin "10") (pinfunction "10_10") (pintype "passive"))
      (node (ref "Siwa_receiver_1") (pin "7") (pinfunction "Pin7_7") (pintype "passive"))
    )
    (net (code "18") (name "GPIO_PAD_0_OUT") (class "Default")
      (node (ref "HEADER_20x2") (pin "9") (pinfunction "9_9") (pintype "passive"))
      (node (ref "LS_1") (pin "4") (pinfunction "SDA_A_4") (pintype "bidirectional"))
    )
    (net (code "19") (name "GPIO_PAD_1") (class "Default")
      (node (ref "HEADER_20x2") (pin "12") (pinfunction "12_12") (pintype "passive"))
      (node (ref "Siwa_receiver_1") (pin "6") (pinfunction "Pin6_6") (pintype "passive"))
    )
    (net (code "20") (name "GPIO_PAD_1_OUT") (class "Default")
      (node (ref "HEADER_20x2") (pin "11") (pinfunction "11_11") (pintype "passive"))
      (node (ref "LS_1") (pin "5") (pinfunction "SCL_A_5") (pintype "bidirectional"))
    )
    (net (code "21") (name "GPIO_PAD_2") (class "Default")
      (node (ref "HEADER_20x2") (pin "14") (pinfunction "14_14") (pintype "passive"))
      (node (ref "Siwa_receiver_1") (pin "4") (pinfunction "Pin4_4") (pintype "passive"))
    )
    (net (code "22") (name "GPIO_PAD_2_OUT") (class "Default")
      (node (ref "HEADER_20x2") (pin "13") (pinfunction "13_13") (pintype "passive"))
      (node (ref "LS_2") (pin "4") (pinfunction "SDA_A_4") (pintype "bidirectional"))
    )
    (net (code "23") (name "GPIO_PAD_3") (class "Default")
      (node (ref "HEADER_20x2") (pin "16") (pinfunction "16_16") (pintype "passive"))
      (node (ref "Siwa_receiver_1") (pin "1") (pinfunction "Pin1_1") (pintype "passive"))
    )
    (net (code "24") (name "GPIO_PAD_3_OUT") (class "Default")
      (node (ref "HEADER_20x2") (pin "15") (pinfunction "15_15") (pintype "passive"))
      (node (ref "LS_2") (pin "5") (pinfunction "SCL_A_5") (pintype "bidirectional"))
    )
    (net (code "25") (name "GPIO_PAD_4") (class "Default")
      (node (ref "HEADER_20x2") (pin "18") (pinfunction "18_18") (pintype "passive"))
      (node (ref "Siwa_receiver_3") (pin "2") (pinfunction "Pin2_2") (pintype "passive"))
    )
    (net (code "26") (name "GPIO_PAD_4_OUT") (class "Default")
      (node (ref "HEADER_20x2") (pin "17") (pinfunction "17_17") (pintype "passive"))
      (node (ref "LS_3") (pin "5") (pinfunction "SCL_A_5") (pintype "bidirectional"))
    )
    (net (code "27") (name "GPIO_PAD_5") (class "Default")
      (node (ref "HEADER_20x2") (pin "20") (pinfunction "20_20") (pintype "passive"))
      (node (ref "Siwa_receiver_3") (pin "3") (pinfunction "Pin3_3") (pintype "passive"))
    )
    (net (code "28") (name "GPIO_PAD_5_OUT") (class "Default")
      (node (ref "HEADER_20x2") (pin "19") (pinfunction "19_19") (pintype "passive"))
      (node (ref "LS_3") (pin "4") (pinfunction "SDA_A_4") (pintype "bidirectional"))
    )
    (net (code "29") (name "GPIO_PAD_6") (class "Default")
      (node (ref "HEADER_20x2") (pin "22") (pinfunction "22_22") (pintype "passive"))
      (node (ref "Siwa_receiver_3") (pin "5") (pinfunction "Pin5_5") (pintype "passive"))
    )
    (net (code "30") (name "GPIO_PAD_6_OUT") (class "Default")
      (node (ref "HEADER_20x2") (pin "21") (pinfunction "21_21") (pintype "passive"))
      (node (ref "LS_4") (pin "5") (pinfunction "SCL_A_5") (pintype "bidirectional"))
    )
    (net (code "31") (name "GPIO_PAD_7") (class "Default")
      (node (ref "HEADER_20x2") (pin "24") (pinfunction "24_24") (pintype "passive"))
      (node (ref "Siwa_receiver_3") (pin "8") (pinfunction "Pin8_8") (pintype "passive"))
    )
    (net (code "32") (name "GPIO_PAD_7_OUT") (class "Default")
      (node (ref "HEADER_20x2") (pin "23") (pinfunction "23_23") (pintype "passive"))
      (node (ref "LS_4") (pin "4") (pinfunction "SDA_A_4") (pintype "bidirectional"))
    )
    (net (code "33") (name "H_LED_4") (class "Default")
      (node (ref "GPIO_BUFFER_LED_3") (pin "6") (pinfunction "1Y_6") (pintype "passive"))
      (node (ref "HEADER_20x2") (pin "34") (pinfunction "34_34") (pintype "passive"))
    )
    (net (code "34") (name "H_LED_5") (class "Default")
      (node (ref "GPIO_BUFFER_LED_3") (pin "4") (pinfunction "2Y_4") (pintype "passive"))
      (node (ref "HEADER_20x2") (pin "36") (pinfunction "36_36") (pintype "passive"))
    )
    (net (code "35") (name "H_LED_6") (class "Default")
      (node (ref "GPIO_BUFFER_LED_4") (pin "6") (pinfunction "1Y_6") (pintype "passive"))
      (node (ref "HEADER_20x2") (pin "38") (pinfunction "38_38") (pintype "passive"))
    )
    (net (code "36") (name "H_LED_7") (class "Default")
      (node (ref "GPIO_BUFFER_LED_4") (pin "4") (pinfunction "2Y_4") (pintype "passive"))
      (node (ref "HEADER_20x2") (pin "40") (pinfunction "40_40") (pintype "passive"))
    )
    (net (code "37") (name "MAIP") (class "Default")
      (node (ref "No_needed_signals") (pin "3") (pinfunction "3_3") (pintype "passive"))
      (node (ref "Siwa_receiver_4") (pin "5") (pinfunction "Pin5_5") (pintype "passive"))
    )
    (net (code "38") (name "Net-(1.0_V_REGULATOR-NR)") (class "Default")
      (node (ref "1.0_V_REGULATOR") (pin "4") (pinfunction "NR_4") (pintype "passive"))
      (node (ref "C_NR1") (pin "2") (pinfunction "2_2") (pintype "passive"))
    )
    (net (code "39") (name "Net-(1.8_V_REGULATOR-BP)") (class "Default")
      (node (ref "1.8_V_REGULATOR") (pin "4") (pinfunction "BP_4") (pintype "passive"))
      (node (ref "C_BP1") (pin "1") (pinfunction "1_1") (pintype "passive"))
    )
    (net (code "40") (name "Net-(3.0_V_REGULATOR-BP)") (class "Default")
      (node (ref "3.0_V_REGULATOR") (pin "4") (pinfunction "BP_4") (pintype "passive"))
      (node (ref "C_BP2") (pin "1") (pinfunction "1_1") (pintype "passive"))
    )
    (net (code "41") (name "Net-(CLK_BUFFER-CLK0)") (class "Default")
      (node (ref "CLK_BUFFER") (pin "4") (pinfunction "CLK0_4") (pintype "input"))
      (node (ref "R_CLK1") (pin "1") (pinfunction "1_1") (pintype "passive"))
    )
    (net (code "42") (name "Net-(CLK_BUFFER-FIN)") (class "Default")
      (node (ref "CLK_BUFFER") (pin "3") (pinfunction "FIN_3") (pintype "input"))
      (node (ref "OSCILLATOR_20MHz") (pin "3") (pinfunction "Output_3") (pintype "output"))
    )
    (net (code "43") (name "Net-(GPIOS_DISPLAY-Pad1)") (class "Default")
      (node (ref "GPIOS_DISPLAY") (pin "1") (pinfunction "1_1") (pintype "passive"))
      (node (ref "OLED_SCREEN_BASE") (pin "5") (pinfunction "5_5") (pintype "passive"))
    )
    (net (code "44") (name "Net-(GPIOS_DISPLAY-Pad3)") (class "Default")
      (node (ref "GPIOS_DISPLAY") (pin "3") (pinfunction "3_3") (pintype "passive"))
      (node (ref "OLED_SCREEN_BASE") (pin "6") (pinfunction "6_6") (pintype "passive"))
    )
    (net (code "45") (name "Net-(GPIOS_DISPLAY-Pad5)") (class "Default")
      (node (ref "GPIOS_DISPLAY") (pin "5") (pinfunction "5_5") (pintype "passive"))
      (node (ref "OLED_SCREEN_BASE") (pin "7") (pinfunction "7_7") (pintype "passive"))
    )
    (net (code "46") (name "Net-(GPIOS_DISPLAY-Pad7)") (class "Default")
      (node (ref "GPIOS_DISPLAY") (pin "7") (pinfunction "7_7") (pintype "passive"))
      (node (ref "OLED_SCREEN_BASE") (pin "4") (pinfunction "4_4") (pintype "passive"))
    )
    (net (code "47") (name "Net-(GPIO_BUFFER1-1A)") (class "Default")
      (node (ref "GPIOS_LEDs_0") (pin "4") (pinfunction "4_4") (pintype "passive"))
      (node (ref "GPIO_BUFFER1") (pin "1") (pinfunction "1A_1") (pintype "passive"))
      (node (ref "LS_OUT_1") (pin "5") (pinfunction "5_5") (pintype "passive"))
    )
    (net (code "48") (name "Net-(GPIO_BUFFER1-1Y)") (class "Default")
      (node (ref "GPIOS_DISPLAY") (pin "6") (pinfunction "6_6") (pintype "passive"))
      (node (ref "GPIO_BUFFER1") (pin "6") (pinfunction "1Y_6") (pintype "passive"))
    )
    (net (code "49") (name "Net-(GPIO_BUFFER1-2A)") (class "Default")
      (node (ref "GPIOS_LEDs_0") (pin "2") (pinfunction "2_2") (pintype "passive"))
      (node (ref "GPIO_BUFFER1") (pin "3") (pinfunction "2A_3") (pintype "passive"))
      (node (ref "LS_OUT_1") (pin "7") (pinfunction "7_7") (pintype "passive"))
    )
    (net (code "50") (name "Net-(GPIO_BUFFER1-2Y)") (class "Default")
      (node (ref "GPIOS_DISPLAY") (pin "8") (pinfunction "8_8") (pintype "passive"))
      (node (ref "GPIO_BUFFER1") (pin "4") (pinfunction "2Y_4") (pintype "passive"))
    )
    (net (code "51") (name "Net-(GPIO_BUFFER2-1A)") (class "Default")
      (node (ref "GPIOS_LEDs_0") (pin "8") (pinfunction "8_8") (pintype "passive"))
      (node (ref "GPIO_BUFFER2") (pin "1") (pinfunction "1A_1") (pintype "passive"))
      (node (ref "LS_OUT_1") (pin "1") (pinfunction "1_1") (pintype "passive"))
    )
    (net (code "52") (name "Net-(GPIO_BUFFER2-1Y)") (class "Default")
      (node (ref "GPIOS_DISPLAY") (pin "2") (pinfunction "2_2") (pintype "passive"))
      (node (ref "GPIO_BUFFER2") (pin "6") (pinfunction "1Y_6") (pintype "passive"))
    )
    (net (code "53") (name "Net-(GPIO_BUFFER2-2A)") (class "Default")
      (node (ref "GPIOS_LEDs_0") (pin "6") (pinfunction "6_6") (pintype "passive"))
      (node (ref "GPIO_BUFFER2") (pin "3") (pinfunction "2A_3") (pintype "passive"))
      (node (ref "LS_OUT_1") (pin "3") (pinfunction "3_3") (pintype "passive"))
    )
    (net (code "54") (name "Net-(GPIO_BUFFER2-2Y)") (class "Default")
      (node (ref "GPIOS_DISPLAY") (pin "4") (pinfunction "4_4") (pintype "passive"))
      (node (ref "GPIO_BUFFER2") (pin "4") (pinfunction "2Y_4") (pintype "passive"))
    )
    (net (code "55") (name "Net-(GPIO_BUFFER_LED_1-1A)") (class "Default")
      (node (ref "GPIOS_LEDs_0") (pin "1") (pinfunction "1_1") (pintype "passive"))
      (node (ref "GPIO_BUFFER_LED_1") (pin "1") (pinfunction "1A_1") (pintype "passive"))
    )
    (net (code "56") (name "Net-(GPIO_BUFFER_LED_1-1Y)") (class "Default")
      (node (ref "GPIO_BUFFER_LED_1") (pin "6") (pinfunction "1Y_6") (pintype "passive"))
      (node (ref "HEADER_20x2") (pin "26") (pinfunction "26_26") (pintype "passive"))
    )
    (net (code "57") (name "Net-(GPIO_BUFFER_LED_1-2A)") (class "Default")
      (node (ref "GPIOS_LEDs_0") (pin "3") (pinfunction "3_3") (pintype "passive"))
      (node (ref "GPIO_BUFFER_LED_1") (pin "3") (pinfunction "2A_3") (pintype "passive"))
    )
    (net (code "58") (name "Net-(GPIO_BUFFER_LED_1-2Y)") (class "Default")
      (node (ref "GPIO_BUFFER_LED_1") (pin "4") (pinfunction "2Y_4") (pintype "passive"))
      (node (ref "HEADER_20x2") (pin "28") (pinfunction "28_28") (pintype "passive"))
    )
    (net (code "59") (name "Net-(GPIO_BUFFER_LED_2-1A)") (class "Default")
      (node (ref "GPIOS_LEDs_0") (pin "5") (pinfunction "5_5") (pintype "passive"))
      (node (ref "GPIO_BUFFER_LED_2") (pin "1") (pinfunction "1A_1") (pintype "passive"))
    )
    (net (code "60") (name "Net-(GPIO_BUFFER_LED_2-1Y)") (class "Default")
      (node (ref "GPIO_BUFFER_LED_2") (pin "6") (pinfunction "1Y_6") (pintype "passive"))
      (node (ref "HEADER_20x2") (pin "30") (pinfunction "30_30") (pintype "passive"))
    )
    (net (code "61") (name "Net-(GPIO_BUFFER_LED_2-2A)") (class "Default")
      (node (ref "GPIOS_LEDs_0") (pin "7") (pinfunction "7_7") (pintype "passive"))
      (node (ref "GPIO_BUFFER_LED_2") (pin "3") (pinfunction "2A_3") (pintype "passive"))
    )
    (net (code "62") (name "Net-(GPIO_BUFFER_LED_2-2Y)") (class "Default")
      (node (ref "GPIO_BUFFER_LED_2") (pin "4") (pinfunction "2Y_4") (pintype "passive"))
      (node (ref "HEADER_20x2") (pin "32") (pinfunction "32_32") (pintype "passive"))
    )
    (net (code "63") (name "Net-(GPIO_BUFFER_LED_3-1A)") (class "Default")
      (node (ref "GPIO_BUFFER_LED_3") (pin "1") (pinfunction "1A_1") (pintype "passive"))
      (node (ref "LS_OUT_2") (pin "1") (pinfunction "1_1") (pintype "passive"))
    )
    (net (code "64") (name "Net-(GPIO_BUFFER_LED_3-2A)") (class "Default")
      (node (ref "GPIO_BUFFER_LED_3") (pin "3") (pinfunction "2A_3") (pintype "passive"))
      (node (ref "LS_OUT_2") (pin "3") (pinfunction "3_3") (pintype "passive"))
    )
    (net (code "65") (name "Net-(GPIO_BUFFER_LED_4-1A)") (class "Default")
      (node (ref "GPIO_BUFFER_LED_4") (pin "1") (pinfunction "1A_1") (pintype "passive"))
      (node (ref "LS_OUT_2") (pin "5") (pinfunction "5_5") (pintype "passive"))
    )
    (net (code "66") (name "Net-(GPIO_BUFFER_LED_4-2A)") (class "Default")
      (node (ref "GPIO_BUFFER_LED_4") (pin "3") (pinfunction "2A_3") (pintype "passive"))
      (node (ref "LS_OUT_2") (pin "7") (pinfunction "7_7") (pintype "passive"))
    )
    (net (code "67") (name "Net-(HEADER_20x2-Pad2)") (class "Default")
      (node (ref "HEADER_20x2") (pin "2") (pinfunction "2_2") (pintype "passive"))
      (node (ref "R_CLK1") (pin "2") (pinfunction "2_2") (pintype "passive"))
    )
    (net (code "68") (name "Net-(LED1-K)") (class "Default")
      (node (ref "LED1") (pin "1") (pinfunction "K_1") (pintype "passive"))
      (node (ref "R_LED_1") (pin "1") (pinfunction "1_1") (pintype "passive"))
    )
    (net (code "69") (name "Net-(LED2-K)") (class "Default")
      (node (ref "LED2") (pin "1") (pinfunction "K_1") (pintype "passive"))
      (node (ref "R_LED_2") (pin "1") (pinfunction "1_1") (pintype "passive"))
    )
    (net (code "70") (name "Net-(LED3-K)") (class "Default")
      (node (ref "LED3") (pin "1") (pinfunction "K_1") (pintype "passive"))
      (node (ref "R_LED_3") (pin "1") (pinfunction "1_1") (pintype "passive"))
    )
    (net (code "71") (name "Net-(LED4-K)") (class "Default")
      (node (ref "LED4") (pin "1") (pinfunction "K_1") (pintype "passive"))
      (node (ref "R_LED_4") (pin "1") (pinfunction "1_1") (pintype "passive"))
    )
    (net (code "72") (name "Net-(LED5-K)") (class "Default")
      (node (ref "LED5") (pin "1") (pinfunction "K_1") (pintype "passive"))
      (node (ref "R_LED_5") (pin "1") (pinfunction "1_1") (pintype "passive"))
    )
    (net (code "73") (name "Net-(LED6-K)") (class "Default")
      (node (ref "LED6") (pin "1") (pinfunction "K_1") (pintype "passive"))
      (node (ref "R_LED_6") (pin "1") (pinfunction "1_1") (pintype "passive"))
    )
    (net (code "74") (name "Net-(LED7-K)") (class "Default")
      (node (ref "LED7") (pin "1") (pinfunction "K_1") (pintype "passive"))
      (node (ref "R_LED_7") (pin "1") (pinfunction "1_1") (pintype "passive"))
    )
    (net (code "75") (name "Net-(LED8-K)") (class "Default")
      (node (ref "LED8") (pin "1") (pinfunction "K_1") (pintype "passive"))
      (node (ref "R_LED_8") (pin "1") (pinfunction "1_1") (pintype "passive"))
    )
    (net (code "76") (name "Net-(LS_1-SCL_B)") (class "Default")
      (node (ref "LS_1") (pin "8") (pinfunction "SCL_B_8") (pintype "bidirectional"))
      (node (ref "LS_OUT_1") (pin "6") (pinfunction "6_6") (pintype "passive"))
    )
    (net (code "77") (name "Net-(LS_1-SDA_B)") (class "Default")
      (node (ref "LS_1") (pin "1") (pinfunction "SDA_B_1") (pintype "bidirectional"))
      (node (ref "LS_OUT_1") (pin "8") (pinfunction "8_8") (pintype "passive"))
    )
    (net (code "78") (name "Net-(LS_2-SCL_B)") (class "Default")
      (node (ref "LS_2") (pin "8") (pinfunction "SCL_B_8") (pintype "bidirectional"))
      (node (ref "LS_OUT_1") (pin "2") (pinfunction "2_2") (pintype "passive"))
    )
    (net (code "79") (name "Net-(LS_2-SDA_B)") (class "Default")
      (node (ref "LS_2") (pin "1") (pinfunction "SDA_B_1") (pintype "bidirectional"))
      (node (ref "LS_OUT_1") (pin "4") (pinfunction "4_4") (pintype "passive"))
    )
    (net (code "80") (name "Net-(LS_3-SCL_B)") (class "Default")
      (node (ref "LS_3") (pin "8") (pinfunction "SCL_B_8") (pintype "bidirectional"))
      (node (ref "LS_OUT_2") (pin "2") (pinfunction "2_2") (pintype "passive"))
    )
    (net (code "81") (name "Net-(LS_3-SDA_B)") (class "Default")
      (node (ref "LS_3") (pin "1") (pinfunction "SDA_B_1") (pintype "bidirectional"))
      (node (ref "LS_OUT_2") (pin "4") (pinfunction "4_4") (pintype "passive"))
    )
    (net (code "82") (name "Net-(LS_4-SCL_B)") (class "Default")
      (node (ref "LS_4") (pin "8") (pinfunction "SCL_B_8") (pintype "bidirectional"))
      (node (ref "LS_OUT_2") (pin "6") (pinfunction "6_6") (pintype "passive"))
    )
    (net (code "83") (name "Net-(LS_4-SDA_B)") (class "Default")
      (node (ref "LS_4") (pin "1") (pinfunction "SDA_B_1") (pintype "bidirectional"))
      (node (ref "LS_OUT_2") (pin "8") (pinfunction "8_8") (pintype "passive"))
    )
    (net (code "84") (name "Net-(RESET_BUFFER-1A)") (class "Default")
      (node (ref "RESET_BUFFER") (pin "1") (pinfunction "1A_1") (pintype "passive"))
      (node (ref "RESET_CIRCUIT") (pin "2") (pinfunction "RESET_2") (pintype "passive"))
    )
    (net (code "85") (name "Net-(RESET_BUFFER-1Y)") (class "Default")
      (node (ref "HEADER_20x2") (pin "6") (pinfunction "6_6") (pintype "passive"))
      (node (ref "RESET_BUFFER") (pin "6") (pinfunction "1Y_6") (pintype "passive"))
    )
    (net (code "86") (name "Net-(RESET_CIRCUIT-~{MR})") (class "Default")
      (node (ref "RESET_CIRCUIT") (pin "3") (pinfunction "~{MR}_3") (pintype "passive"))
      (node (ref "SW1") (pin "2") (pinfunction "P2_2") (pintype "passive"))
    )
    (net (code "87") (name "Net-(Siwa_receiver_2-Pin6)") (class "Default")
      (node (ref "MEMORY_CONNECTOR") (pin "6") (pinfunction "6_6") (pintype "passive"))
      (node (ref "Siwa_receiver_2") (pin "6") (pinfunction "Pin6_6") (pintype "passive"))
    )
    (net (code "88") (name "Net-(Siwa_receiver_2-Pin7)") (class "Default")
      (node (ref "MEMORY_CONNECTOR") (pin "5") (pinfunction "5_5") (pintype "passive"))
      (node (ref "Siwa_receiver_2") (pin "7") (pinfunction "Pin7_7") (pintype "passive"))
    )
    (net (code "89") (name "Net-(Siwa_receiver_2-Pin8)") (class "Default")
      (node (ref "MEMORY_CONNECTOR") (pin "2") (pinfunction "2_2") (pintype "passive"))
      (node (ref "Siwa_receiver_2") (pin "8") (pinfunction "Pin8_8") (pintype "passive"))
    )
    (net (code "90") (name "Net-(Siwa_receiver_4-Pin3)") (class "Default")
      (node (ref "HEADER_20x2") (pin "1") (pinfunction "1_1") (pintype "passive"))
      (node (ref "HEADER_20x2") (pin "3") (pinfunction "3_3") (pintype "passive"))
      (node (ref "Siwa_receiver_4") (pin "3") (pinfunction "Pin3_3") (pintype "passive"))
    )
    (net (code "91") (name "Net-(Siwa_receiver_4-Pin6)") (class "Default")
      (node (ref "HEADER_20x2") (pin "5") (pinfunction "5_5") (pintype "passive"))
      (node (ref "HEADER_20x2") (pin "7") (pinfunction "7_7") (pintype "passive"))
      (node (ref "Siwa_receiver_4") (pin "6") (pinfunction "Pin6_6") (pintype "passive"))
    )
    (net (code "92") (name "Net-(Siwa_receiver_4-Pin8)") (class "Default")
      (node (ref "MEMORY_CONNECTOR") (pin "1") (pinfunction "1_1") (pintype "passive"))
      (node (ref "Siwa_receiver_4") (pin "8") (pinfunction "Pin8_8") (pintype "passive"))
    )
    (net (code "93") (name "POC_CONTROL") (class "Default")
      (node (ref "No_needed_signals") (pin "1") (pinfunction "1_1") (pintype "passive"))
      (node (ref "Siwa_receiver_4") (pin "4") (pinfunction "Pin4_4") (pintype "passive"))
    )
    (net (code "94") (name "UART_RX") (class "Default")
      (node (ref "No_needed_signals") (pin "7") (pinfunction "7_7") (pintype "passive"))
      (node (ref "Siwa_receiver_2") (pin "4") (pinfunction "Pin4_4") (pintype "passive"))
    )
    (net (code "95") (name "UART_TX") (class "Default")
      (node (ref "No_needed_signals") (pin "5") (pinfunction "5_5") (pintype "passive"))
      (node (ref "Siwa_receiver_2") (pin "2") (pinfunction "Pin2_2") (pintype "passive"))
    )
    (net (code "96") (name "unconnected-(HEADER_20x2-4-Pad4{slash}EXTERNAL_CLK)") (class "Default")
      (node (ref "HEADER_20x2") (pin "4/EXTERNAL_CLK") (pinfunction "4_4/EXTERNAL_CLK") (pintype "passive"))
    )
    (net (code "97") (name "unconnected-(HEADER_20x2-8-Pad8{slash}EXTERNAL_RESET)") (class "Default")
      (node (ref "HEADER_20x2") (pin "8/EXTERNAL_RESET") (pinfunction "8_8/EXTERNAL_RESET") (pintype "passive"))
    )
    (net (code "98") (name "unconnected-(OLED_SCREEN_BASE-Pad8)") (class "Default")
      (node (ref "OLED_SCREEN_BASE") (pin "8") (pinfunction "8_8") (pintype "passive"))
    )
    (net (code "99") (name "unconnected-(RESET_BUFFER-2A-Pad3)") (class "Default")
      (node (ref "RESET_BUFFER") (pin "3") (pinfunction "2A_3") (pintype "passive"))
    )
    (net (code "100") (name "unconnected-(RESET_BUFFER-2Y-Pad4)") (class "Default")
      (node (ref "RESET_BUFFER") (pin "4") (pinfunction "2Y_4") (pintype "passive"))
    )
    (net (code "101") (name "unconnected-(SW1-P1-Pad1)") (class "Default")
      (node (ref "SW1") (pin "1") (pinfunction "P1_1") (pintype "passive"))
    )
    (net (code "102") (name "unconnected-(SW1-P3-Pad3)") (class "Default")
      (node (ref "SW1") (pin "3") (pinfunction "P3_3") (pintype "passive"))
    )
  )
)
